# connectors.net
KiCad netlist of a schematic drawn in Altium Designer
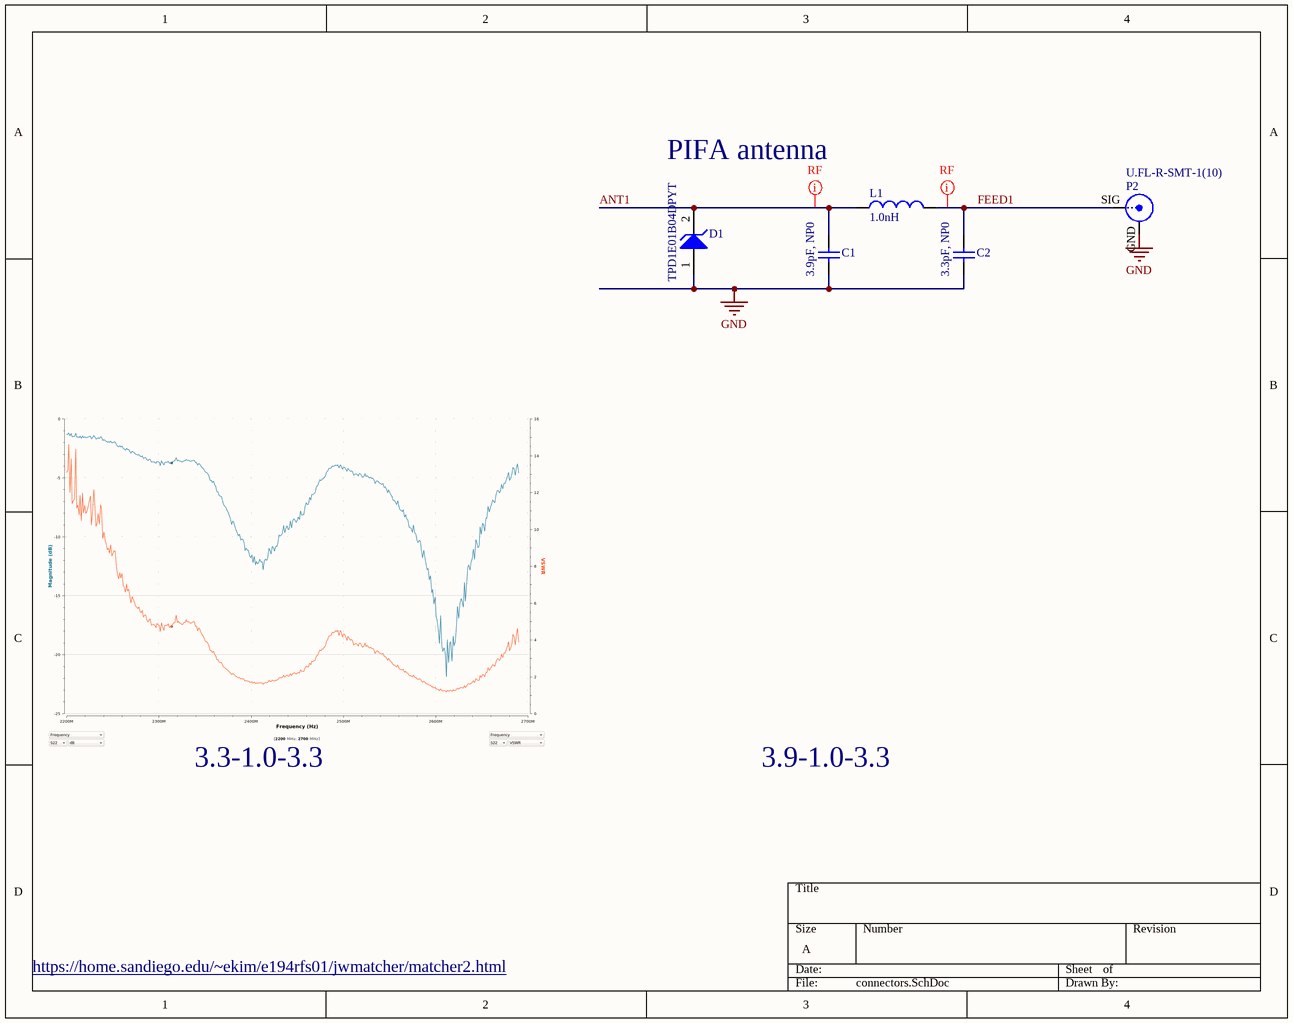
[diagram p0: connectors.SchDoc]

(export (version "E")
  (design (tool "Eeschema 10.0.6"))
  (components
    (comp (ref "C1")
      (value "3.9pF, NP0")
      (footprint "B_CAP0402")
      (description "Capacitor (Semiconductor SIM Model)")
      (fields (field (name "MPN") "CL05C3R9CB5NNNC"))
      (libsource (lib "Miscellaneous Devices") (part "Cap Semi"))
    )
    (comp (ref "C2")
      (value "3.3pF, NP0")
      (footprint "B_CAP0402")
      (description "Capacitor (Semiconductor SIM Model)")
      (fields (field (name "MPN") "GRM1555C1H3R3CA01D"))
      (libsource (lib "Miscellaneous Devices") (part "Cap Semi"))
    )
    (comp (ref "D1")
      (value "TPD1E01B04DPYT")
      (footprint "TI_PX1SON-N2")
      (description "CPDUR24V")
      (fields (field (name "PUBLISHER") "Altium Limited"))
      (libsource (lib "Miscellaneous Devices") (part "D Zener"))
    )
    (comp (ref "L1")
      (value "1.0nH")
      (footprint "B_IND0402")
      (description "Inductor")
      (fields (field (name "MPN") "LQG15HS1N0S02D") (field (name "PUBLISHER") "Altium Limited"))
      (libsource (lib "Miscellaneous Devices") (part "Inductor"))
    )
    (comp (ref "P2")
      (value "U.FL-R-SMT-1(10)")
      (footprint "HRS_U.FL")
      (description "BNC Elbow Connector")
      (fields (field (name "MPN") "P1163-0140R") (field (name "PUBLISHER") "Altium Limited"))
      (libsource (lib "Miscellaneous Connectors") (part "BNC"))
    )
  )
  (nets
    (net (code "1") (name "/ANT1") (class "Default")
      (node (ref "C1") (pin "1") (pinfunction "1_1") (pintype "passive"))
      (node (ref "D1") (pin "2") (pinfunction "K_2") (pintype "passive"))
      (node (ref "L1") (pin "1") (pinfunction "1_1") (pintype "passive"))
    )
    (net (code "2") (name "/FEED1") (class "Default")
      (node (ref "C2") (pin "1") (pinfunction "1_1") (pintype "passive"))
      (node (ref "L1") (pin "2") (pinfunction "2_2") (pintype "passive"))
      (node (ref "P2") (pin "SIG") (pinfunction "X_SIG") (pintype "passive"))
    )
    (net (code "3") (name "GND") (class "Default")
      (node (ref "C1") (pin "2") (pinfunction "2_2") (pintype "passive"))
      (node (ref "C2") (pin "2") (pinfunction "2_2") (pintype "passive"))
      (node (ref "D1") (pin "1") (pinfunction "A_1") (pintype "passive"))
      (node (ref "P2") (pin "GND") (pinfunction "Y_GND") (pintype "passive"))
    )
  )
)
